# AQS.net
KiCad netlist of a schematic drawn in EAGLE
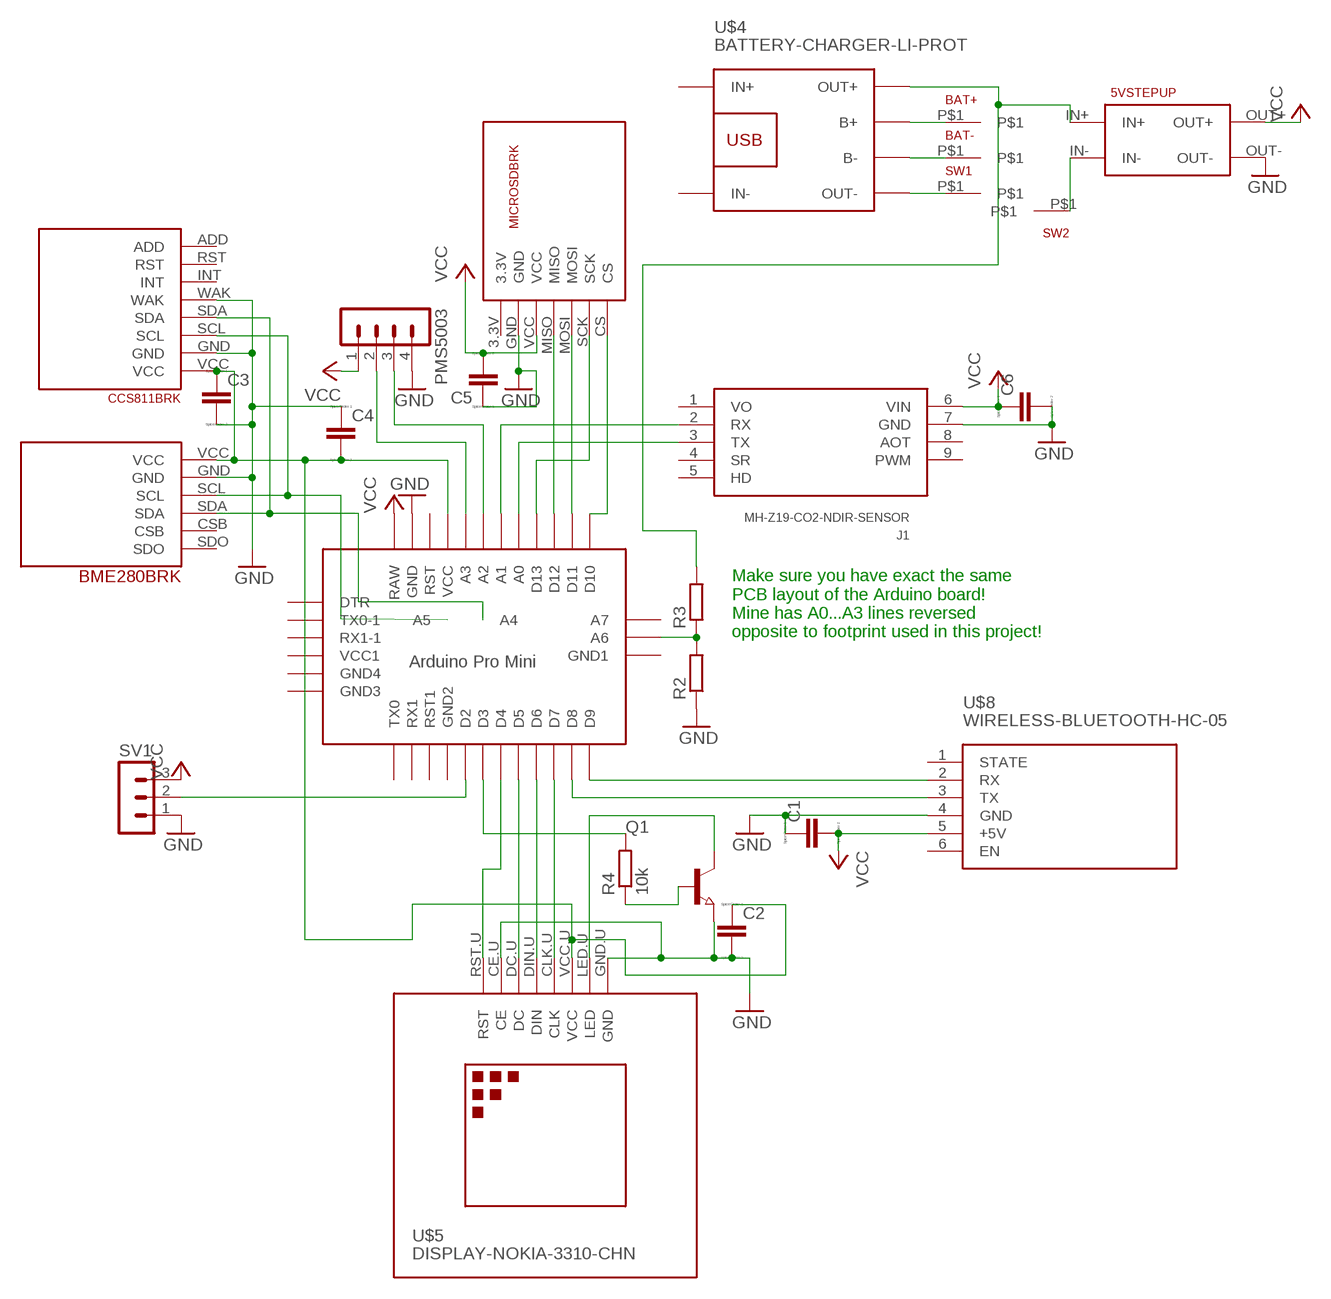
[diagram p0: schematic, sheet 1]

(export (version "E")
  (design (tool "Eeschema 10.0.6"))
  (components
    (comp (ref "BAT+")
      (value "PIN")
      (footprint "eagle-import:PIN")
      (libsource (lib "eagle-import") (part "PIN"))
    )
    (comp (ref "BAT-")
      (value "PIN")
      (footprint "eagle-import:PIN")
      (libsource (lib "eagle-import") (part "PIN"))
    )
    (comp (ref "C1")
      (value "CC1206")
      (footprint "eagle-import:C1206")
      (libsource (lib "eagle-import") (part "CC1206"))
    )
    (comp (ref "C2")
      (value "CC1206")
      (footprint "eagle-import:C1206")
      (libsource (lib "eagle-import") (part "CC1206"))
    )
    (comp (ref "C3")
      (value "CC1206")
      (footprint "eagle-import:C1206")
      (libsource (lib "eagle-import") (part "CC1206"))
    )
    (comp (ref "C4")
      (value "CC1206")
      (footprint "eagle-import:C1206")
      (libsource (lib "eagle-import") (part "CC1206"))
    )
    (comp (ref "C5")
      (value "CC1206")
      (footprint "eagle-import:C1206")
      (libsource (lib "eagle-import") (part "CC1206"))
    )
    (comp (ref "C6")
      (value "CC1206")
      (footprint "eagle-import:C1206")
      (libsource (lib "eagle-import") (part "CC1206"))
    )
    (comp (ref "J1")
      (value "MH-Z19-CO2-NDIR-SENSOR")
      (footprint "eagle-import:MH-Z19")
      (libsource (lib "eagle-import") (part "MH-Z19-CO2-NDIR-SENSOR"))
    )
    (comp (ref "PMS5003")
      (value "MA04-1")
      (footprint "eagle-import:MA04-1")
      (libsource (lib "eagle-import") (part "MA04-1"))
    )
    (comp (ref "Q1")
      (value "NPN-TRANSISTOR_SOT23")
      (footprint "eagle-import:SOT23")
      (libsource (lib "eagle-import") (part "NPN-TRANSISTOR_SOT23"))
    )
    (comp (ref "R2")
      (value "R-EU_0207/10")
      (footprint "eagle-import:0207_10")
      (libsource (lib "eagle-import") (part "R-EU_0207/10"))
    )
    (comp (ref "R3")
      (value "R-EU_0207/10")
      (footprint "eagle-import:0207_10")
      (libsource (lib "eagle-import") (part "R-EU_0207/10"))
    )
    (comp (ref "R4")
      (value "10k")
      (footprint "eagle-import:0207_10")
      (libsource (lib "eagle-import") (part "resistor_348_R-EU_0207/10"))
    )
    (comp (ref "SV1")
      (value "MA03-1")
      (footprint "eagle-import:MA03-1")
      (libsource (lib "eagle-import") (part "MA03-1"))
    )
    (comp (ref "SW1")
      (value "PIN")
      (footprint "eagle-import:PIN")
      (libsource (lib "eagle-import") (part "PIN"))
    )
    (comp (ref "SW2")
      (value "PIN")
      (footprint "eagle-import:PIN")
      (libsource (lib "eagle-import") (part "PIN"))
    )
    (comp (ref "U$1")
      (value "ABK-PRO-MINI")
      (footprint "eagle-import:ABK-PRO-MINI")
      (libsource (lib "eagle-import") (part "ABK-PRO-MINI"))
    )
    (comp (ref "U$2")
      (value "BME280BRK")
      (footprint "eagle-import:BME280BRK")
      (libsource (lib "eagle-import") (part "BME280BRK"))
    )
    (comp (ref "U$3")
      (value "5VSTEPUP")
      (footprint "eagle-import:5VSTEPUP")
      (libsource (lib "eagle-import") (part "5VSTEPUP"))
    )
    (comp (ref "U$4")
      (value "BATTERY-CHARGER-LI-PROT")
      (footprint "eagle-import:BATTERY-CHARGER-LI-PROT")
      (libsource (lib "eagle-import") (part "BATTERY-CHARGER-LI-PROT"))
    )
    (comp (ref "U$5")
      (value "DISPLAY-NOKIA-3310-CHN")
      (footprint "eagle-import:DISPLAY-NOKIA-3310-CHN")
      (libsource (lib "eagle-import") (part "DISPLAY-NOKIA-3310-CHN"))
    )
    (comp (ref "U$6")
      (value "CCS811BRK")
      (footprint "eagle-import:CCS811BRK")
      (libsource (lib "eagle-import") (part "CCS811BRK"))
    )
    (comp (ref "U$7")
      (value "MICROSDBRK")
      (footprint "eagle-import:MICROSDBRK")
      (libsource (lib "eagle-import") (part "MICROSDBRK"))
    )
    (comp (ref "U$8")
      (value "WIRELESS-BLUETOOTH-HC-05")
      (footprint "eagle-import:WIRELESS-BLUETOOTH-HC-05")
      (libsource (lib "eagle-import") (part "WIRELESS-BLUETOOTH-HC-05"))
    )
  )
  (nets
    (net (code "1") (name "/3.3V") (class "Default")
      (node (ref "U$7") (pin "3.3V") (pinfunction "3.3V_3.3V") (pintype "power_in"))
    )
    (net (code "2") (name "/VO") (class "Default")
      (node (ref "J1") (pin "1") (pinfunction "VO_1") (pintype "power_in"))
    )
    (net (code "3") (name "GND") (class "Default")
      (node (ref "C1") (pin "1") (pinfunction "1_1") (pintype "passive"))
      (node (ref "C2") (pin "2") (pinfunction "2_2") (pintype "passive"))
      (node (ref "C3") (pin "2") (pinfunction "2_2") (pintype "passive"))
      (node (ref "C4") (pin "1") (pinfunction "1_1") (pintype "passive"))
      (node (ref "C5") (pin "1") (pinfunction "1_1") (pintype "passive"))
      (node (ref "C6") (pin "2") (pinfunction "2_2") (pintype "passive"))
      (node (ref "J1") (pin "7") (pinfunction "GND_7") (pintype "power_in"))
      (node (ref "PMS5003") (pin "4") (pinfunction "4_4") (pintype "passive"))
      (node (ref "Q1") (pin "2") (pinfunction "E_2") (pintype "passive"))
      (node (ref "R2") (pin "1") (pinfunction "1_1") (pintype "passive"))
      (node (ref "SV1") (pin "1") (pinfunction "1_1") (pintype "passive"))
      (node (ref "U$1") (pin "GND") (pinfunction "GND_GND") (pintype "bidirectional"))
      (node (ref "U$2") (pin "GND") (pinfunction "GND_GND") (pintype "power_in"))
      (node (ref "U$3") (pin "OUT-") (pinfunction "OUT-_OUT-") (pintype "bidirectional"))
      (node (ref "U$5") (pin "CE.U") (pinfunction "CE_CE.U") (pintype "input"))
      (node (ref "U$5") (pin "GND.U") (pinfunction "GND_GND.U") (pintype "power_in"))
      (node (ref "U$6") (pin "GND") (pinfunction "GND_GND") (pintype "bidirectional"))
      (node (ref "U$6") (pin "WAK") (pinfunction "WAK_WAK") (pintype "bidirectional"))
      (node (ref "U$7") (pin "GND") (pinfunction "GND_GND") (pintype "power_in"))
      (node (ref "U$8") (pin "4") (pinfunction "GND_4") (pintype "power_in"))
    )
    (net (code "4") (name "Net-(BAT+-PadP$1)") (class "Default")
      (node (ref "BAT+") (pin "P$1") (pinfunction "P$1_P$1") (pintype "bidirectional"))
      (node (ref "U$4") (pin "B+") (pinfunction "B+_B+") (pintype "bidirectional"))
    )
    (net (code "5") (name "Net-(BAT--PadP$1)") (class "Default")
      (node (ref "BAT-") (pin "P$1") (pinfunction "P$1_P$1") (pintype "bidirectional"))
      (node (ref "U$4") (pin "B-") (pinfunction "B-_B-") (pintype "bidirectional"))
    )
    (net (code "6") (name "Net-(J1-RX)") (class "Default")
      (node (ref "J1") (pin "2") (pinfunction "RX_2") (pintype "input"))
      (node (ref "U$1") (pin "A1") (pinfunction "A1_A1") (pintype "bidirectional"))
    )
    (net (code "7") (name "Net-(J1-TX)") (class "Default")
      (node (ref "J1") (pin "3") (pinfunction "TX_3") (pintype "output"))
      (node (ref "U$1") (pin "A0") (pinfunction "A0_A0") (pintype "bidirectional"))
    )
    (net (code "8") (name "Net-(PMS5003-Pad2)") (class "Default")
      (node (ref "PMS5003") (pin "2") (pinfunction "2_2") (pintype "passive"))
      (node (ref "U$1") (pin "A3") (pinfunction "A3_A3") (pintype "bidirectional"))
    )
    (net (code "9") (name "Net-(PMS5003-Pad3)") (class "Default")
      (node (ref "PMS5003") (pin "3") (pinfunction "3_3") (pintype "passive"))
      (node (ref "U$1") (pin "A2") (pinfunction "A2_A2") (pintype "bidirectional"))
    )
    (net (code "10") (name "Net-(Q1-B)") (class "Default")
      (node (ref "Q1") (pin "1") (pinfunction "B_1") (pintype "passive"))
      (node (ref "R4") (pin "1") (pinfunction "1_1") (pintype "passive"))
    )
    (net (code "11") (name "Net-(Q1-C)") (class "Default")
      (node (ref "Q1") (pin "3") (pinfunction "C_3") (pintype "passive"))
      (node (ref "U$5") (pin "LED.U") (pinfunction "LED_LED.U") (pintype "bidirectional"))
    )
    (net (code "12") (name "Net-(R2-Pad2)") (class "Default")
      (node (ref "R2") (pin "2") (pinfunction "2_2") (pintype "passive"))
      (node (ref "R3") (pin "1") (pinfunction "1_1") (pintype "passive"))
      (node (ref "U$1") (pin "A6") (pinfunction "A6_A6") (pintype "bidirectional"))
    )
    (net (code "13") (name "Net-(R3-Pad2)") (class "Default")
      (node (ref "R3") (pin "2") (pinfunction "2_2") (pintype "passive"))
      (node (ref "U$3") (pin "IN+") (pinfunction "IN+_IN+") (pintype "bidirectional"))
      (node (ref "U$4") (pin "OUT+") (pinfunction "OUT+_OUT+") (pintype "bidirectional"))
    )
    (net (code "14") (name "Net-(R4-Pad2)") (class "Default")
      (node (ref "R4") (pin "2") (pinfunction "2_2") (pintype "passive"))
      (node (ref "U$1") (pin "D3") (pinfunction "D3_D3") (pintype "bidirectional"))
    )
    (net (code "15") (name "Net-(SV1-Pad2)") (class "Default")
      (node (ref "SV1") (pin "2") (pinfunction "2_2") (pintype "passive"))
      (node (ref "U$1") (pin "D2") (pinfunction "D2_D2") (pintype "bidirectional"))
    )
    (net (code "16") (name "Net-(SW1-PadP$1)") (class "Default")
      (node (ref "SW1") (pin "P$1") (pinfunction "P$1_P$1") (pintype "bidirectional"))
      (node (ref "U$4") (pin "OUT-") (pinfunction "OUT-_OUT-") (pintype "bidirectional"))
    )
    (net (code "17") (name "Net-(SW2-PadP$1)") (class "Default")
      (node (ref "SW2") (pin "P$1") (pinfunction "P$1_P$1") (pintype "bidirectional"))
      (node (ref "U$3") (pin "IN-") (pinfunction "IN-_IN-") (pintype "bidirectional"))
    )
    (net (code "18") (name "Net-(U$1-PadA4)") (class "Default")
      (node (ref "U$1") (pin "A4") (pinfunction "A4_A4") (pintype "bidirectional"))
      (node (ref "U$2") (pin "SDA") (pinfunction "SDA_SDA") (pintype "bidirectional"))
      (node (ref "U$6") (pin "SDA") (pinfunction "SDA_SDA") (pintype "bidirectional"))
    )
    (net (code "19") (name "Net-(U$1-PadA5)") (class "Default")
      (node (ref "U$1") (pin "A5") (pinfunction "A5_A5") (pintype "bidirectional"))
      (node (ref "U$2") (pin "SCL") (pinfunction "SCL_SCL") (pintype "bidirectional"))
      (node (ref "U$6") (pin "SCL") (pinfunction "SCL_SCL") (pintype "bidirectional"))
    )
    (net (code "20") (name "Net-(U$1-PadD10)") (class "Default")
      (node (ref "U$1") (pin "D10") (pinfunction "D10_D10") (pintype "bidirectional"))
      (node (ref "U$7") (pin "CS") (pinfunction "CS_CS") (pintype "bidirectional"))
    )
    (net (code "21") (name "Net-(U$1-PadD11)") (class "Default")
      (node (ref "U$1") (pin "D11") (pinfunction "D11_D11") (pintype "bidirectional"))
      (node (ref "U$7") (pin "MOSI") (pinfunction "MOSI_MOSI") (pintype "bidirectional"))
    )
    (net (code "22") (name "Net-(U$1-PadD12)") (class "Default")
      (node (ref "U$1") (pin "D12") (pinfunction "D12_D12") (pintype "bidirectional"))
      (node (ref "U$7") (pin "MISO") (pinfunction "MISO_MISO") (pintype "bidirectional"))
    )
    (net (code "23") (name "Net-(U$1-PadD13)") (class "Default")
      (node (ref "U$1") (pin "D13") (pinfunction "D13_D13") (pintype "bidirectional"))
      (node (ref "U$7") (pin "SCK") (pinfunction "SCK_SCK") (pintype "bidirectional"))
    )
    (net (code "24") (name "Net-(U$5-CLK)") (class "Default")
      (node (ref "U$1") (pin "D7") (pinfunction "D7_D7") (pintype "bidirectional"))
      (node (ref "U$5") (pin "CLK.U") (pinfunction "CLK_CLK.U") (pintype "bidirectional"))
    )
    (net (code "25") (name "Net-(U$5-DC)") (class "Default")
      (node (ref "U$1") (pin "D5") (pinfunction "D5_D5") (pintype "bidirectional"))
      (node (ref "U$5") (pin "DC.U") (pinfunction "DC_DC.U") (pintype "bidirectional"))
    )
    (net (code "26") (name "Net-(U$5-DIN)") (class "Default")
      (node (ref "U$1") (pin "D6") (pinfunction "D6_D6") (pintype "bidirectional"))
      (node (ref "U$5") (pin "DIN.U") (pinfunction "DIN_DIN.U") (pintype "bidirectional"))
    )
    (net (code "27") (name "Net-(U$5-RST)") (class "Default")
      (node (ref "U$1") (pin "D4") (pinfunction "D4_D4") (pintype "bidirectional"))
      (node (ref "U$5") (pin "RST.U") (pinfunction "RST_RST.U") (pintype "input"))
    )
    (net (code "28") (name "Net-(U$5-VCC)") (class "Default")
      (node (ref "C2") (pin "1") (pinfunction "1_1") (pintype "passive"))
      (node (ref "C3") (pin "1") (pinfunction "1_1") (pintype "passive"))
      (node (ref "C4") (pin "2") (pinfunction "2_2") (pintype "passive"))
      (node (ref "U$1") (pin "VCC") (pinfunction "VCC_VCC") (pintype "bidirectional"))
      (node (ref "U$2") (pin "VCC") (pinfunction "VCC_VCC") (pintype "power_in"))
      (node (ref "U$5") (pin "VCC.U") (pinfunction "VCC_VCC.U") (pintype "power_in"))
      (node (ref "U$6") (pin "VCC") (pinfunction "VCC_VCC") (pintype "bidirectional"))
    )
    (net (code "29") (name "Net-(U$8-RX)") (class "Default")
      (node (ref "U$1") (pin "D9") (pinfunction "D9_D9") (pintype "bidirectional"))
      (node (ref "U$8") (pin "2") (pinfunction "RX_2") (pintype "bidirectional"))
    )
    (net (code "30") (name "Net-(U$8-TX)") (class "Default")
      (node (ref "U$1") (pin "D8") (pinfunction "D8_D8") (pintype "bidirectional"))
      (node (ref "U$8") (pin "3") (pinfunction "TX_3") (pintype "bidirectional"))
    )
    (net (code "31") (name "VCC") (class "Default")
      (node (ref "C1") (pin "2") (pinfunction "2_2") (pintype "passive"))
      (node (ref "C5") (pin "2") (pinfunction "2_2") (pintype "passive"))
      (node (ref "C6") (pin "1") (pinfunction "1_1") (pintype "passive"))
      (node (ref "J1") (pin "6") (pinfunction "VIN_6") (pintype "power_in"))
      (node (ref "PMS5003") (pin "1") (pinfunction "1_1") (pintype "passive"))
      (node (ref "SV1") (pin "3") (pinfunction "3_3") (pintype "passive"))
      (node (ref "U$1") (pin "RAW") (pinfunction "RAW_RAW") (pintype "bidirectional"))
      (node (ref "U$3") (pin "OUT+") (pinfunction "OUT+_OUT+") (pintype "bidirectional"))
      (node (ref "U$7") (pin "VCC") (pinfunction "VCC_VCC") (pintype "power_in"))
      (node (ref "U$8") (pin "5") (pinfunction "+5V_5") (pintype "power_in"))
    )
    (net (code "32") (name "unconnected-(J1-AOT-Pad8)") (class "Default")
      (node (ref "J1") (pin "8") (pinfunction "AOT_8") (pintype "no_connect"))
    )
    (net (code "33") (name "unconnected-(J1-HD-Pad5)") (class "Default")
      (node (ref "J1") (pin "5") (pinfunction "HD_5") (pintype "input"))
    )
    (net (code "34") (name "unconnected-(J1-PWM-Pad9)") (class "Default")
      (node (ref "J1") (pin "9") (pinfunction "PWM_9") (pintype "output"))
    )
    (net (code "35") (name "unconnected-(J1-SR-Pad4)") (class "Default")
      (node (ref "J1") (pin "4") (pinfunction "SR_4") (pintype "no_connect"))
    )
    (net (code "36") (name "unconnected-(U$1-GND1-PadGND4)") (class "Default")
      (node (ref "U$1") (pin "GND4") (pinfunction "GND1_GND4") (pintype "bidirectional"))
    )
    (net (code "37") (name "unconnected-(U$1-GND2-PadGND1)") (class "Default")
      (node (ref "U$1") (pin "GND1") (pinfunction "GND2_GND1") (pintype "bidirectional"))
    )
    (net (code "38") (name "unconnected-(U$1-GND3-PadGND2)") (class "Default")
      (node (ref "U$1") (pin "GND2") (pinfunction "GND3_GND2") (pintype "bidirectional"))
    )
    (net (code "39") (name "unconnected-(U$1-GND4-PadGND3)") (class "Default")
      (node (ref "U$1") (pin "GND3") (pinfunction "GND4_GND3") (pintype "bidirectional"))
    )
    (net (code "40") (name "unconnected-(U$1-PadA7)") (class "Default")
      (node (ref "U$1") (pin "A7") (pinfunction "A7_A7") (pintype "bidirectional"))
    )
    (net (code "41") (name "unconnected-(U$1-PadDTR)") (class "Default")
      (node (ref "U$1") (pin "DTR") (pinfunction "DTR_DTR") (pintype "bidirectional"))
    )
    (net (code "42") (name "unconnected-(U$1-PadRST)") (class "Default")
      (node (ref "U$1") (pin "RST") (pinfunction "RST_RST") (pintype "bidirectional"))
    )
    (net (code "43") (name "unconnected-(U$1-PadRST1)") (class "Default")
      (node (ref "U$1") (pin "RST1") (pinfunction "RST1_RST1") (pintype "bidirectional"))
    )
    (net (code "44") (name "unconnected-(U$1-PadRX1)") (class "Default")
      (node (ref "U$1") (pin "RX1") (pinfunction "RX1_RX1") (pintype "bidirectional"))
    )
    (net (code "45") (name "unconnected-(U$1-PadRX1-1)") (class "Default")
      (node (ref "U$1") (pin "RX1-1") (pinfunction "RX1-1_RX1-1") (pintype "bidirectional"))
    )
    (net (code "46") (name "unconnected-(U$1-PadTX0)") (class "Default")
      (node (ref "U$1") (pin "TX0") (pinfunction "TX0_TX0") (pintype "bidirectional"))
    )
    (net (code "47") (name "unconnected-(U$1-PadTX0-1)") (class "Default")
      (node (ref "U$1") (pin "TX0-1") (pinfunction "TX0-1_TX0-1") (pintype "bidirectional"))
    )
    (net (code "48") (name "unconnected-(U$1-PadVCC1)") (class "Default")
      (node (ref "U$1") (pin "VCC1") (pinfunction "VCC1_VCC1") (pintype "bidirectional"))
    )
    (net (code "49") (name "unconnected-(U$2-PadCSB)") (class "Default")
      (node (ref "U$2") (pin "CSB") (pinfunction "CSB_CSB") (pintype "bidirectional"))
    )
    (net (code "50") (name "unconnected-(U$2-PadSDO)") (class "Default")
      (node (ref "U$2") (pin "SDO") (pinfunction "SDO_SDO") (pintype "bidirectional"))
    )
    (net (code "51") (name "unconnected-(U$4-PadIN+)") (class "Default")
      (node (ref "U$4") (pin "IN+") (pinfunction "IN+_IN+") (pintype "bidirectional"))
    )
    (net (code "52") (name "unconnected-(U$4-PadIN-)") (class "Default")
      (node (ref "U$4") (pin "IN-") (pinfunction "IN-_IN-") (pintype "bidirectional"))
    )
    (net (code "53") (name "unconnected-(U$6-PadADD)") (class "Default")
      (node (ref "U$6") (pin "ADD") (pinfunction "ADD_ADD") (pintype "bidirectional"))
    )
    (net (code "54") (name "unconnected-(U$6-PadINT)") (class "Default")
      (node (ref "U$6") (pin "INT") (pinfunction "INT_INT") (pintype "bidirectional"))
    )
    (net (code "55") (name "unconnected-(U$6-PadRST)") (class "Default")
      (node (ref "U$6") (pin "RST") (pinfunction "RST_RST") (pintype "bidirectional"))
    )
    (net (code "56") (name "unconnected-(U$8-EN-Pad6)") (class "Default")
      (node (ref "U$8") (pin "6") (pinfunction "EN_6") (pintype "bidirectional"))
    )
    (net (code "57") (name "unconnected-(U$8-STATE-Pad1)") (class "Default")
      (node (ref "U$8") (pin "1") (pinfunction "STATE_1") (pintype "bidirectional"))
    )
  )
)
